# POWER.net
KiCad netlist of a schematic drawn in Altium Designer
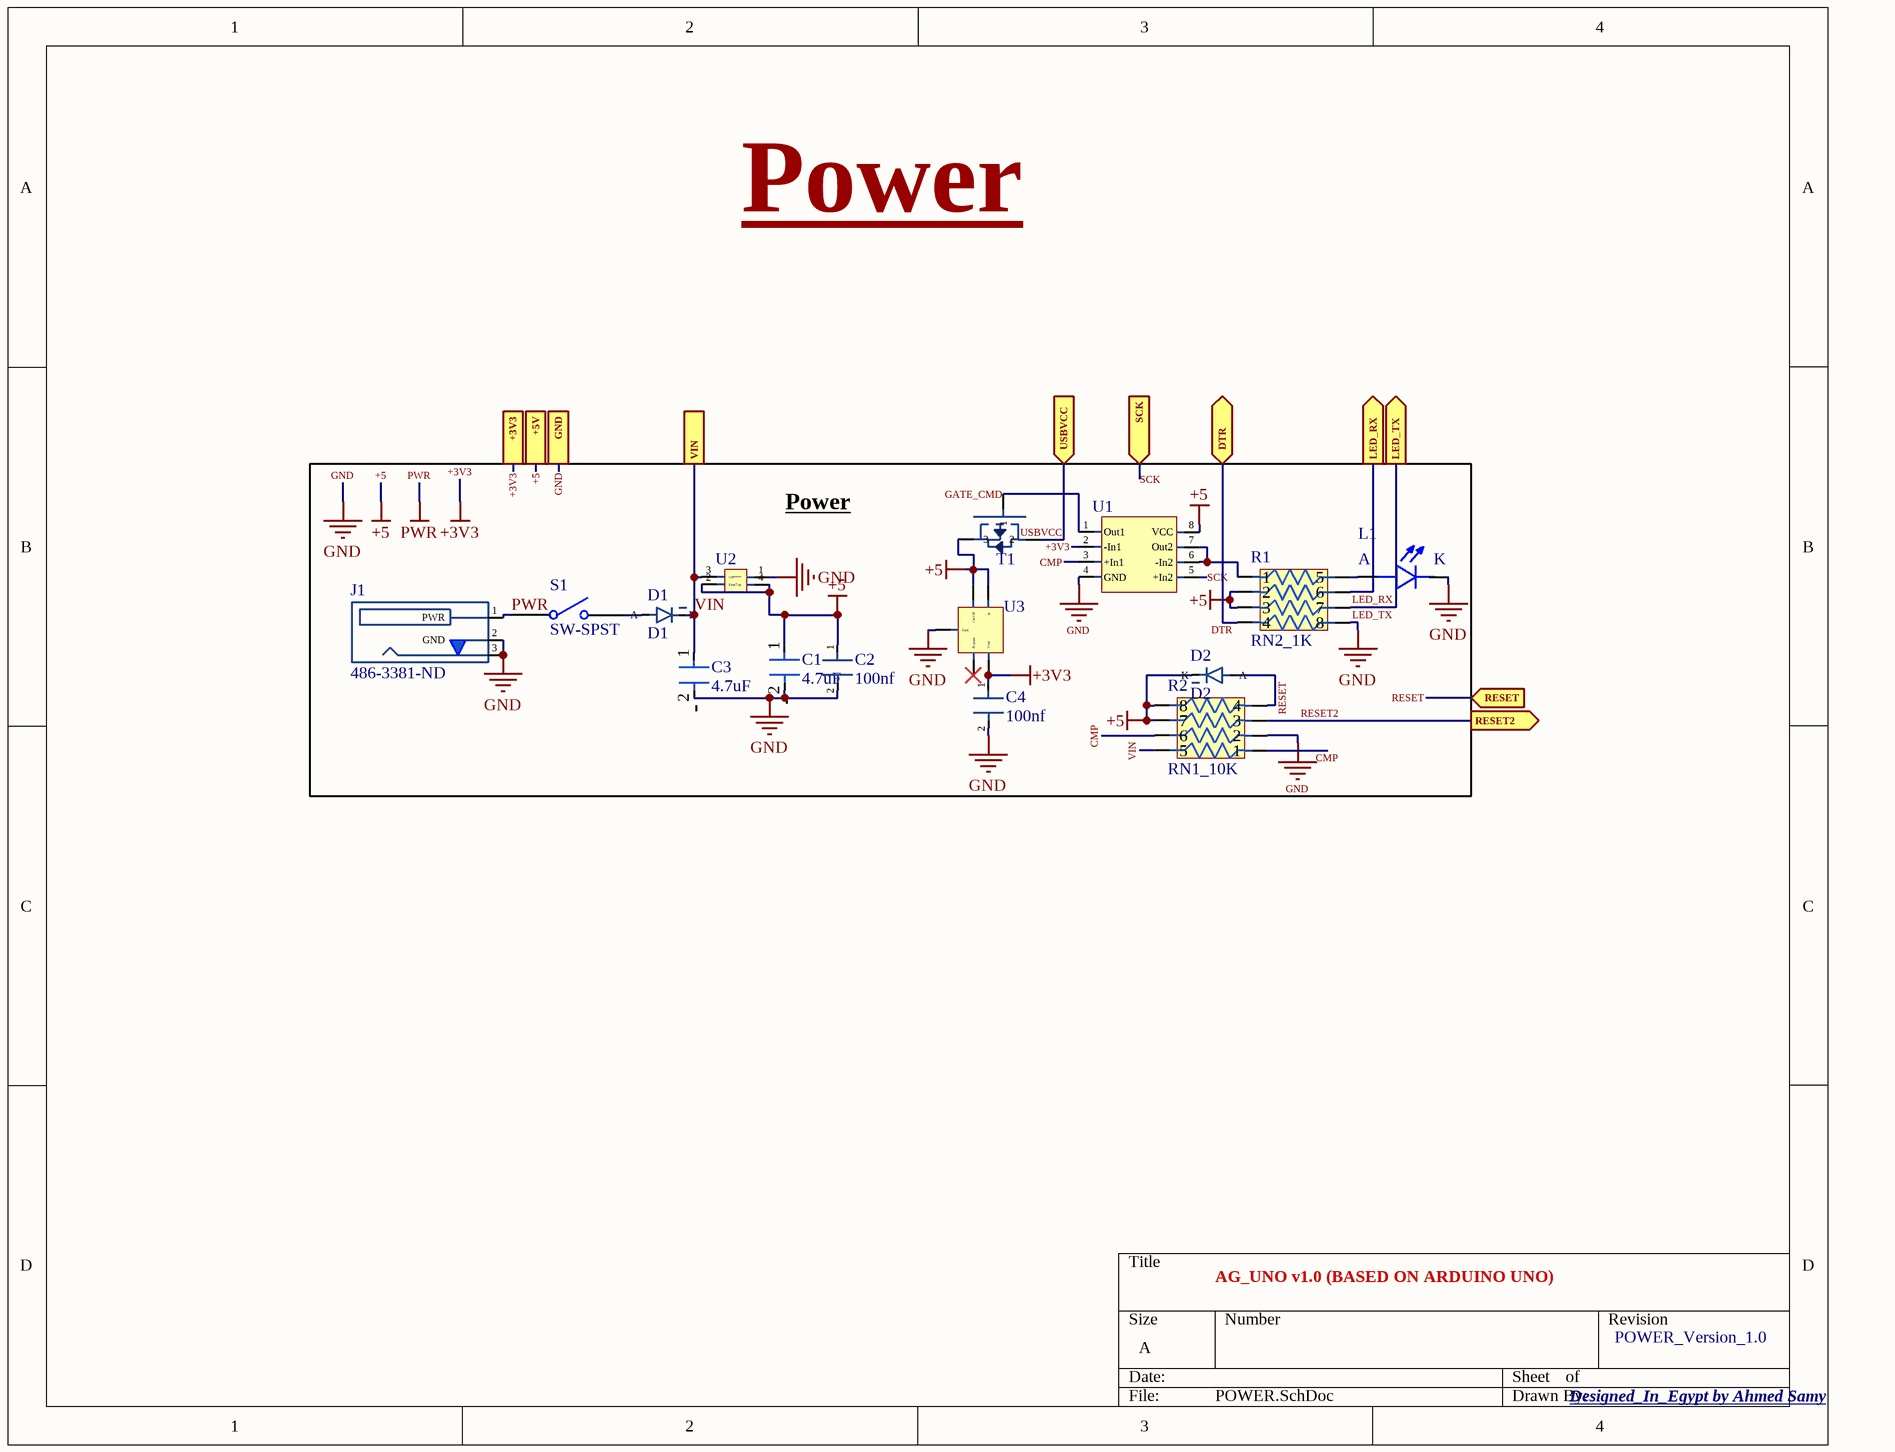
[diagram p0: POWER.SchDoc]

(export (version "E")
  (design (tool "Eeschema 10.0.6"))
  (components
    (comp (ref "C1")
      (value "4.7uF")
      (footprint "P16437CT-ND")
      (description "CAP ALUM POLY 4.7UF 20% 10V SMD")
      (libsource (lib "Task") (part "P16437CT-ND"))
    )
    (comp (ref "C2")
      (value "100nf")
      (footprint "CC0603KRX7R7BB105")
      (description "1 µF ±10% 16V Ceramic Capacitor X7R 0603 (1608 Metric)")
      (libsource (lib "Task") (part "CC0603KRX7R7BB105"))
    )
    (comp (ref "C3")
      (value "4.7uF")
      (footprint "P16437CT-ND")
      (description "CAP ALUM POLY 4.7UF 20% 10V SMD")
      (libsource (lib "Task") (part "P16437CT-ND"))
    )
    (comp (ref "C4")
      (value "100nf")
      (footprint "CC0603KRX7R7BB105")
      (description "1 µF ±10% 16V Ceramic Capacitor X7R 0603 (1608 Metric)")
      (libsource (lib "Task") (part "CC0603KRX7R7BB105"))
    )
    (comp (ref "D1")
      (value "D1")
      (footprint "CGRA4007-G")
      (description "Diode 1000 V 1A Surface Mount DO-214AC (SMA) [used in UNO]")
      (libsource (lib "Task") (part "CGRA4007-G"))
    )
    (comp (ref "D2")
      (value "D2")
      (footprint "CD1206-S01575")
      (description "Diode 100 V 150mA Surface Mount 1206 [D2 UNO]")
      (libsource (lib "Task") (part "CD1206-S01575"))
    )
    (comp (ref "J1")
      (value "486-3381-ND")
      (footprint "486-3381-ND")
      (description "Power Barrel Connector Jack 2.10mm ID (0.083\"), 5.50mm OD (0.217\") Through Hole, Right Angle")
      (libsource (lib "Task") (part "486-3381-ND"))
    )
    (comp (ref "L1")
      (value "LED_OPAMP")
      (footprint "LED_Q62702P5179")
      (description "LED 0805")
      (libsource (lib "Task") (part "LED_Q62702P5179"))
    )
    (comp (ref "R1")
      (value "RN2_1K")
      (footprint "CAY16-103J4GLF")
      (libsource (lib "Task") (part "CAY16-103J4GLF"))
    )
    (comp (ref "R2")
      (value "RN1_10K")
      (footprint "CAY16-103J4GLF")
      (libsource (lib "") (part "CAY16-103J4GLF_1"))
    )
    (comp (ref "S1")
      (value "SW-SPST")
      (footprint "SPST-2")
      (description "Single-Pole, Single-Throw Switch")
      (fields (field (name "PUBLISHER") "Altium Limited"))
      (libsource (lib "Miscellaneous Devices") (part "SW-SPST"))
    )
    (comp (ref "T1")
      (value "IRLML6402TRPBF")
      (footprint "IRLML6402TRPBF")
      (description "P-Channel 20 V 3.7A (Ta) 1.3W (Ta) Surface Mount Micro3™/SOT-23")
      (libsource (lib "Task") (part "IRLML6402TRPBF"))
    )
    (comp (ref "U1")
      (value "LMV358LIST")
      (footprint "LMV358LIST")
      (description "General Purpose Amplifier 2 Circuit Rail-to-Rail 8-MiniSO")
      (libsource (lib "Task") (part "LMV358LIST"))
    )
    (comp (ref "U2")
      (value "SPX1117M3-L-5-0/TR")
      (footprint "SPX1117M3-L-5-0/TR")
      (description "Linear Voltage Regulator IC Positive Fixed 1 Output 800mA SOT-223-3")
      (libsource (lib "Task") (part "SPX1117M3-L-5-0/TR"))
    )
    (comp (ref "U3")
      (value "LP2985-33DBVR")
      (footprint "LP2985-33DBVR")
      (description "Linear Voltage Regulator IC Positive Fixed 1 Output 150mA SOT-23-5")
      (libsource (lib "Task") (part "LP2985-33DBVR"))
    )
  )
  (nets
    (net (code "1") (name "+3V3") (class "Default")
      (node (ref "C4") (pin "1") (pinfunction "1_1") (pintype "passive"))
      (node (ref "U1") (pin "2") (pinfunction "-In1_2") (pintype "input"))
      (node (ref "U3") (pin "5") (pinfunction "Vout_5") (pintype "output"))
    )
    (net (code "2") (name "+5") (class "Default")
      (node (ref "C1") (pin "1") (pintype "passive"))
      (node (ref "C2") (pin "1") (pinfunction "1_1") (pintype "passive"))
      (node (ref "D2") (pin "1") (pinfunction "K_1") (pintype "passive"))
      (node (ref "R1") (pin "2") (pinfunction "2_2") (pintype "passive"))
      (node (ref "R1") (pin "3") (pinfunction "3_3") (pintype "passive"))
      (node (ref "R2") (pin "7") (pinfunction "7_7") (pintype "passive"))
      (node (ref "R2") (pin "8") (pinfunction "8_8") (pintype "passive"))
      (node (ref "T1") (pin "3") (pinfunction "3_3") (pintype "passive"))
      (node (ref "U1") (pin "8") (pinfunction "VCC_8") (pintype "passive"))
      (node (ref "U2") (pin "2") (pinfunction "Vout_2") (pintype "passive"))
      (node (ref "U2") (pin "4") (pinfunction "Tap_4") (pintype "passive"))
      (node (ref "U3") (pin "1") (pinfunction "In_1") (pintype "input"))
      (node (ref "U3") (pin "3") (pinfunction "On/Off_3") (pintype "input"))
    )
    (net (code "3") (name "/CMP") (class "Default")
      (node (ref "R2") (pin "1") (pinfunction "1_1") (pintype "passive"))
      (node (ref "R2") (pin "6") (pinfunction "6_6") (pintype "passive"))
      (node (ref "U1") (pin "3") (pinfunction "+In1_3") (pintype "input"))
    )
    (net (code "4") (name "/DTR") (class "Default")
      (node (ref "R1") (pin "4") (pinfunction "4_4") (pintype "passive"))
    )
    (net (code "5") (name "/GATE_CMD") (class "Default")
      (node (ref "T1") (pin "1") (pinfunction "1_1") (pintype "passive"))
      (node (ref "U1") (pin "1") (pinfunction "Out1_1") (pintype "output"))
    )
    (net (code "6") (name "/LED_RX") (class "Default")
      (node (ref "R1") (pin "6") (pinfunction "6_6") (pintype "passive"))
    )
    (net (code "7") (name "/LED_TX") (class "Default")
      (node (ref "R1") (pin "7") (pinfunction "7_7") (pintype "passive"))
    )
    (net (code "8") (name "/RESET") (class "Default")
      (node (ref "D2") (pin "2") (pinfunction "A_2") (pintype "passive"))
      (node (ref "R2") (pin "4") (pinfunction "4_4") (pintype "passive"))
    )
    (net (code "9") (name "/RESET2") (class "Default")
      (node (ref "R2") (pin "3") (pinfunction "3_3") (pintype "passive"))
    )
    (net (code "10") (name "/SCK") (class "Default")
      (node (ref "U1") (pin "5") (pinfunction "+In2_5") (pintype "input"))
    )
    (net (code "11") (name "/USBVCC") (class "Default")
      (node (ref "T1") (pin "2") (pinfunction "2_2") (pintype "passive"))
    )
    (net (code "12") (name "/VIN") (class "Default")
      (node (ref "C3") (pin "1") (pintype "passive"))
      (node (ref "D1") (pin "1") (pinfunction "K_1") (pintype "passive"))
      (node (ref "R2") (pin "5") (pinfunction "5_5") (pintype "passive"))
      (node (ref "U2") (pin "3") (pinfunction "Vin_3") (pintype "input"))
    )
    (net (code "13") (name "GND") (class "Default")
      (node (ref "C1") (pin "2") (pinfunction "-_2") (pintype "passive"))
      (node (ref "C2") (pin "2") (pinfunction "2_2") (pintype "passive"))
      (node (ref "C3") (pin "2") (pinfunction "-_2") (pintype "passive"))
      (node (ref "C4") (pin "2") (pinfunction "2_2") (pintype "passive"))
      (node (ref "J1") (pin "2") (pinfunction "GND_2") (pintype "passive"))
      (node (ref "J1") (pin "3") (pintype "passive"))
      (node (ref "L1") (pin "C") (pinfunction "C_C") (pintype "passive"))
      (node (ref "R1") (pin "8") (pinfunction "8_8") (pintype "passive"))
      (node (ref "R2") (pin "2") (pinfunction "2_2") (pintype "passive"))
      (node (ref "U1") (pin "4") (pinfunction "GND_4") (pintype "power_in"))
      (node (ref "U2") (pin "1") (pinfunction "GND/ADJ_1") (pintype "passive"))
      (node (ref "U3") (pin "2") (pinfunction "Gnd_2") (pintype "power_in"))
    )
    (net (code "14") (name "Net-(D1-A)") (class "Default")
      (node (ref "D1") (pin "2") (pinfunction "A_2") (pintype "passive"))
      (node (ref "S1") (pin "2") (pinfunction "NO_2") (pintype "passive"))
    )
    (net (code "15") (name "Net-(L1-PadA)") (class "Default")
      (node (ref "L1") (pin "A") (pinfunction "A_A") (pintype "passive"))
      (node (ref "R1") (pin "5") (pinfunction "5_5") (pintype "passive"))
    )
    (net (code "16") (name "Net-(U1--In2)") (class "Default")
      (node (ref "R1") (pin "1") (pinfunction "1_1") (pintype "passive"))
      (node (ref "U1") (pin "6") (pinfunction "-In2_6") (pintype "input"))
      (node (ref "U1") (pin "7") (pinfunction "Out2_7") (pintype "output"))
    )
    (net (code "17") (name "PWR") (class "Default")
      (node (ref "J1") (pin "1") (pinfunction "PWR_1") (pintype "passive"))
      (node (ref "S1") (pin "1") (pinfunction "COMMON_1") (pintype "passive"))
    )
    (net (code "18") (name "unconnected-(U3-Bypass-Pad4)") (class "Default")
      (node (ref "U3") (pin "4") (pinfunction "Bypass_4") (pintype "bidirectional+no_connect"))
    )
  )
)
